# can.net
KiCad netlist of a schematic drawn in Altium Designer
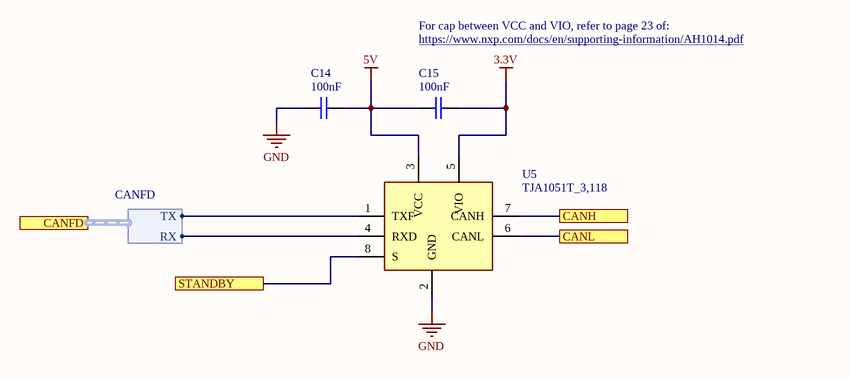
[diagram p0: can.SchDoc]

(export (version "E")
  (design (tool "Eeschema 10.0.6"))
  (components
    (comp (ref "C14")
      (value "100nF")
      (footprint "0603 - Capacitor")
      (description "Nonpolarized Capacitor")
      (fields (field (name "Comment") "Capacitor - Nonpolarized"))
      (libsource (lib "General") (part "Capacitor - Nonpolarized"))
    )
    (comp (ref "C15")
      (value "100nF")
      (footprint "0603 - Capacitor")
      (description "Nonpolarized Capacitor")
      (fields (field (name "Comment") "Capacitor - Nonpolarized"))
      (libsource (lib "General") (part "Capacitor - Nonpolarized"))
    )
    (comp (ref "U5")
      (value "TJA1051T_3,118")
      (footprint "TJA1051T/3,118 - duplicate")
      (description "CAN Transceiver IC 4.5V-5.5V 250ns")
      (fields (field (name "MANUFACTURER") "NXP") (field (name "MANUFACTURER PART NUMBER") "TJA1051T/3,118"))
      (libsource (lib "GeneralComponents") (part "TJA1051T_3,118"))
    )
  )
  (nets
    (net (code "2") (name "/CANH") (class "Default")
      (node (ref "U5") (pin "7") (pinfunction "CANH_7") (pintype "passive"))
    )
    (net (code "3") (name "/CANL") (class "Default")
      (node (ref "U5") (pin "6") (pinfunction "CANL_6") (pintype "passive"))
    )
    (net (code "4") (name "/RX") (class "Default")
      (node (ref "U5") (pin "4") (pinfunction "RXD_4") (pintype "passive"))
    )
    (net (code "5") (name "/STANDBY") (class "Default")
      (node (ref "U5") (pin "8") (pinfunction "S_8") (pintype "passive"))
    )
    (net (code "6") (name "/TX") (class "Default")
      (node (ref "U5") (pin "1") (pinfunction "TXF_1") (pintype "passive"))
    )
    (net (code "8") (name "3.3V") (class "Default")
      (node (ref "C15") (pin "2") (pinfunction "2_2") (pintype "passive"))
      (node (ref "U5") (pin "5") (pinfunction "VIO_5") (pintype "passive"))
    )
    (net (code "9") (name "5V") (class "Default")
      (node (ref "C14") (pin "2") (pinfunction "2_2") (pintype "passive"))
      (node (ref "C15") (pin "1") (pinfunction "1_1") (pintype "passive"))
      (node (ref "U5") (pin "3") (pinfunction "VCC_3") (pintype "passive"))
    )
    (net (code "10") (name "GND") (class "Default")
      (node (ref "C14") (pin "1") (pinfunction "1_1") (pintype "passive"))
      (node (ref "U5") (pin "2") (pinfunction "GND_2") (pintype "passive"))
    )
  )
)
